# amp.net
KiCad netlist of a schematic drawn in Altium Designer
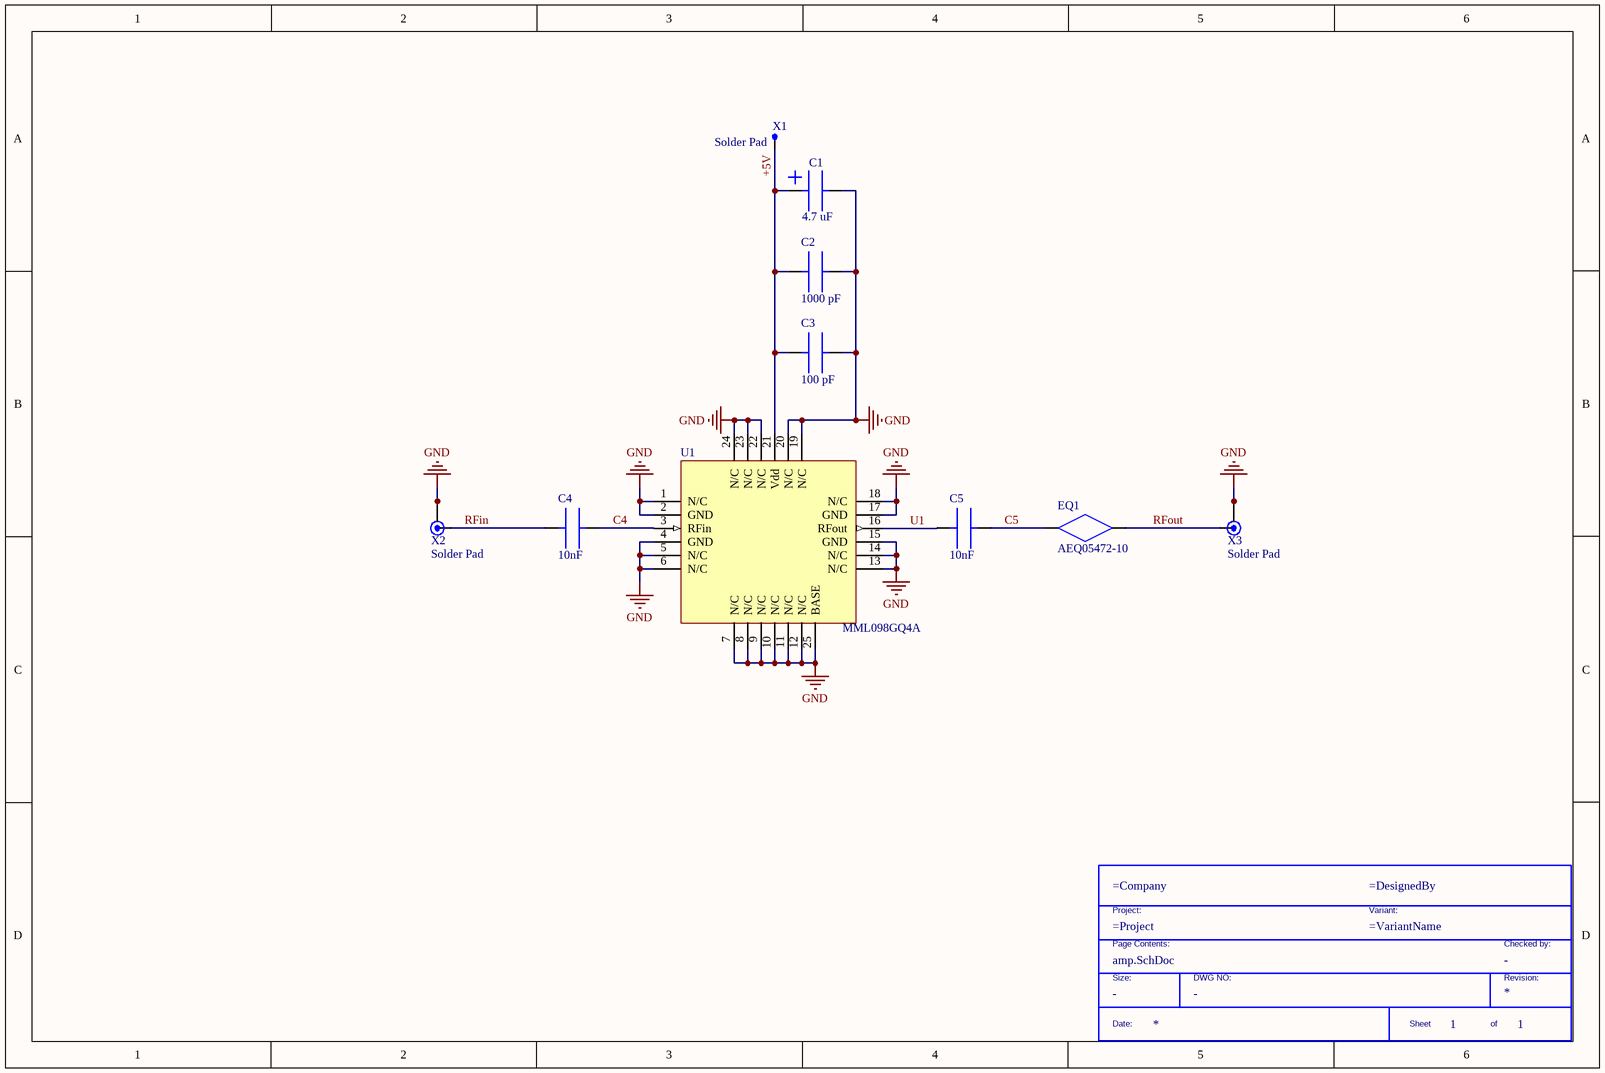
[diagram p0: amp.SchDoc]

(export (version "E")
  (design (tool "Eeschema 10.0.6"))
  (components
    (comp (ref "*")
      (value "TitleBlock")
      (description "Standard Title Block")
      (fields (field (name "DWG NO") "-") (field (name "SIZE") "-") (field (name "CHECKED BY") "-"))
      (libsource (lib "amp") (part "TitleBlock"))
    )
    (comp (ref "C1")
      (value "4.7 uF")
      (footprint "C4_7uF")
      (fields
        (field (name "MANUFACTURER") "Vishay Sprague")
        (field (name "MANUFACTURER PART NUMBER") "TH3A475K010C2900")
      )
      (libsource (lib "amp") (part "C7_4uF_TH3A475K010C2900"))
    )
    (comp (ref "C2")
      (value "1000 pF")
      (footprint "C1000pF__C100nF")
      (fields
        (field (name "MANUFACTURER") "Murata")
        (field (name "MANUFACTURER PART NUMBER") "GCM1885C1H102FA16D")
      )
      (libsource (lib "amp") (part "C1000pF_GCM1885C1H102FA16D"))
    )
    (comp (ref "C3")
      (value "100 pF")
      (footprint "C100pF")
      (description "Multilayer Ceramic Capacitors MLCC - SMD/SMT 100 pF 100 VDC 1% 0402 C0G (NP0)")
      (fields
        (field (name "MANUFACTURER") "Murata")
        (field (name "MANUFACTURER PART NUMBER") "GRM1555C2A101FA01D")
      )
      (libsource (lib "amp") (part "C100pF_GRM1555C2A101FA01D"))
    )
    (comp (ref "C4")
      (value "10nF")
      (footprint "C10nF")
      (fields (field (name "MANUFACTURER") "Murata") (field (name "MANUFACTURER PART NUMBER") "939113733510"))
      (libsource (lib "amp") (part "C10nF_939113733510"))
    )
    (comp (ref "C5")
      (value "10nF")
      (footprint "C10nF")
      (fields (field (name "MANUFACTURER") "Murata") (field (name "MANUFACTURER PART NUMBER") "939113733510"))
      (libsource (lib "amp") (part "C10nF_939113733510"))
    )
    (comp (ref "EQ1")
      (value "AEQ05472-10")
      (footprint "EQ_AEQ05472")
      (description "Rf Filter Gain Equalizer 2SMD")
      (fields (field (name "MANUFACTURER") "Knowles Dielectric Labs"))
      (libsource (lib "amp") (part "EQ_AEQ05472-10"))
    )
    (comp (ref "U1")
      (value "MML098GQ4A")
      (footprint "amp_MML098GQ4A")
      (libsource (lib "amp") (part "amp_MML098GQ4A"))
    )
    (comp (ref "X1")
      (value "Solder Pad")
      (footprint "Solder Pad")
      (description "Pad to solder wires to")
      (libsource (lib "amp") (part "Solder Pad"))
    )
    (comp (ref "X2")
      (value "Solder Pad")
      (footprint "CPW Edge Connector")
      (description "Solder pad for RF Coplanar Waveguide Rogers 4350B Thickness 0.020\" Copper 1oz")
      (libsource (lib "amp") (part "RF  CPW Solder Pad"))
    )
    (comp (ref "X3")
      (value "Solder Pad")
      (footprint "CPW Edge Connector")
      (description "Solder pad for RF Coplanar Waveguide Rogers 4350B Thickness 0.020\" Copper 1oz")
      (libsource (lib "amp") (part "RF  CPW Solder Pad"))
    )
  )
  (nets
    (net (code "1") (name "/+5V") (class "Default")
      (node (ref "C1") (pin "1") (pinfunction "+_1") (pintype "passive"))
      (node (ref "C2") (pin "1") (pinfunction "1_1") (pintype "passive"))
      (node (ref "C3") (pin "1") (pinfunction "1_1") (pintype "passive"))
      (node (ref "U1") (pin "21") (pinfunction "Vdd_21") (pintype "power_in"))
      (node (ref "X1") (pin "1") (pinfunction "1_1") (pintype "passive"))
    )
    (net (code "2") (name "/C4") (class "Default")
      (node (ref "C4") (pin "2") (pinfunction "2_2") (pintype "passive"))
      (node (ref "U1") (pin "3") (pinfunction "RFin_3") (pintype "input"))
    )
    (net (code "3") (name "/C5") (class "Default")
      (node (ref "C5") (pin "2") (pinfunction "2_2") (pintype "passive"))
      (node (ref "EQ1") (pin "1") (pinfunction "1_1") (pintype "passive"))
    )
    (net (code "4") (name "/RFin") (class "Default")
      (node (ref "C4") (pin "1") (pinfunction "1_1") (pintype "passive"))
      (node (ref "X2") (pin "1") (pinfunction "1_1") (pintype "passive"))
    )
    (net (code "5") (name "/RFout") (class "Default")
      (node (ref "EQ1") (pin "2") (pinfunction "2_2") (pintype "passive"))
      (node (ref "X3") (pin "1") (pinfunction "1_1") (pintype "passive"))
    )
    (net (code "6") (name "/U1") (class "Default")
      (node (ref "C5") (pin "1") (pinfunction "1_1") (pintype "passive"))
      (node (ref "U1") (pin "16") (pinfunction "RFout_16") (pintype "output"))
    )
    (net (code "7") (name "GND") (class "Default")
      (node (ref "C1") (pin "2") (pinfunction "2_2") (pintype "passive"))
      (node (ref "C2") (pin "2") (pinfunction "2_2") (pintype "passive"))
      (node (ref "C3") (pin "2") (pinfunction "2_2") (pintype "passive"))
      (node (ref "U1") (pin "1") (pinfunction "N/C_1") (pintype "passive"))
      (node (ref "U1") (pin "10") (pinfunction "N/C_10") (pintype "passive"))
      (node (ref "U1") (pin "11") (pinfunction "N/C_11") (pintype "passive"))
      (node (ref "U1") (pin "12") (pinfunction "N/C_12") (pintype "passive"))
      (node (ref "U1") (pin "13") (pinfunction "N/C_13") (pintype "passive"))
      (node (ref "U1") (pin "14") (pinfunction "N/C_14") (pintype "passive"))
      (node (ref "U1") (pin "15") (pinfunction "GND_15") (pintype "power_in"))
      (node (ref "U1") (pin "17") (pinfunction "GND_17") (pintype "power_in"))
      (node (ref "U1") (pin "18") (pinfunction "N/C_18") (pintype "passive"))
      (node (ref "U1") (pin "19") (pinfunction "N/C_19") (pintype "passive"))
      (node (ref "U1") (pin "2") (pinfunction "GND_2") (pintype "power_in"))
      (node (ref "U1") (pin "20") (pinfunction "N/C_20") (pintype "passive"))
      (node (ref "U1") (pin "22") (pinfunction "N/C_22") (pintype "passive"))
      (node (ref "U1") (pin "23") (pinfunction "N/C_23") (pintype "passive"))
      (node (ref "U1") (pin "24") (pinfunction "N/C_24") (pintype "passive"))
      (node (ref "U1") (pin "25") (pinfunction "BASE_25") (pintype "power_in"))
      (node (ref "U1") (pin "4") (pinfunction "GND_4") (pintype "power_in"))
      (node (ref "U1") (pin "5") (pinfunction "N/C_5") (pintype "passive"))
      (node (ref "U1") (pin "6") (pinfunction "N/C_6") (pintype "passive"))
      (node (ref "U1") (pin "7") (pinfunction "N/C_7") (pintype "passive"))
      (node (ref "U1") (pin "8") (pinfunction "N/C_8") (pintype "passive"))
      (node (ref "U1") (pin "9") (pinfunction "N/C_9") (pintype "passive"))
      (node (ref "X2") (pin "2") (pinfunction "2_2") (pintype "passive"))
      (node (ref "X2") (pin "3") (pinfunction "3_3") (pintype "passive"))
      (node (ref "X3") (pin "2") (pinfunction "2_2") (pintype "passive"))
      (node (ref "X3") (pin "3") (pinfunction "3_3") (pintype "passive"))
    )
  )
)
